# hacklace.net
KiCad netlist of a schematic drawn in EAGLE
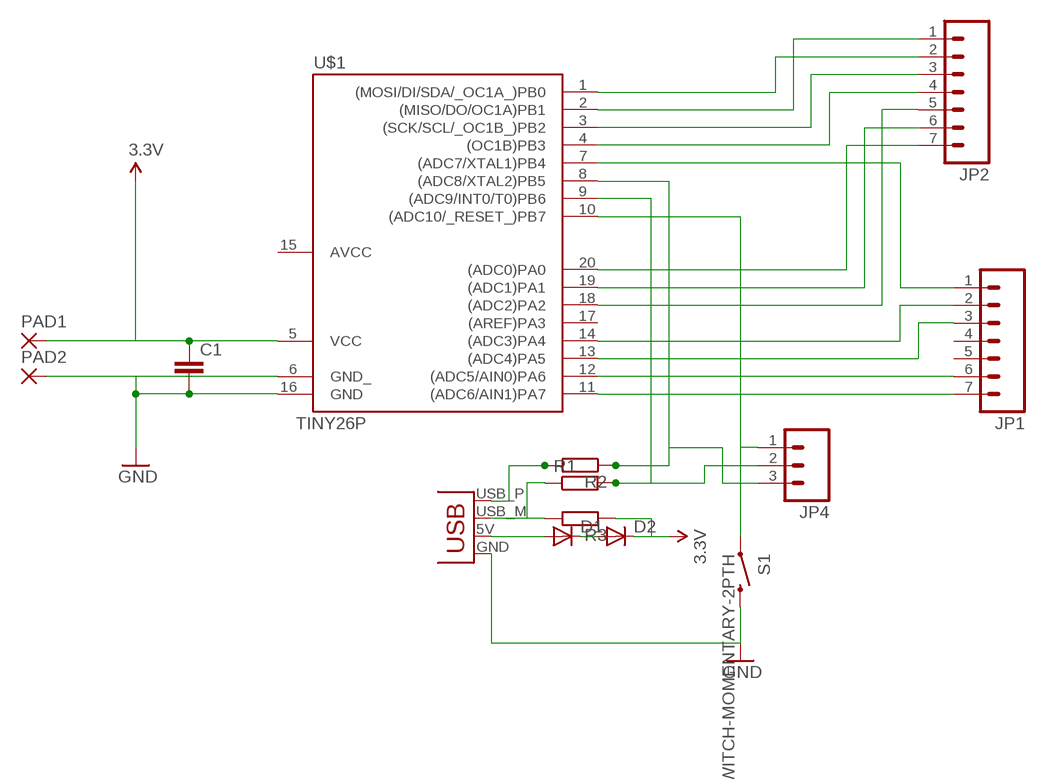
[diagram p0: schematic, sheet 1]

(export (version "E")
  (design (tool "Eeschema 10.0.6"))
  (components
    (comp (ref "C1")
      (value "C-EU025-025X050")
      (footprint "eagle-import:C025-025X050")
      (libsource (lib "eagle-import") (part "C-EU025-025X050"))
    )
    (comp (ref "D1")
      (value "DIODE-D-5")
      (footprint "eagle-import:D-5")
      (libsource (lib "eagle-import") (part "DIODE-D-5"))
    )
    (comp (ref "D2")
      (value "DIODE-D-5")
      (footprint "eagle-import:D-5")
      (libsource (lib "eagle-import") (part "DIODE-D-5"))
    )
    (comp (ref "JP1")
      (value "M07")
      (footprint "eagle-import:1X07")
      (libsource (lib "eagle-import") (part "M07"))
    )
    (comp (ref "JP2")
      (value "M07")
      (footprint "eagle-import:1X07")
      (libsource (lib "eagle-import") (part "M07"))
    )
    (comp (ref "JP3")
      (value "USBPCB")
      (footprint "eagle-import:USB-A-PCB")
      (libsource (lib "eagle-import") (part "USBPCB"))
    )
    (comp (ref "JP4")
      (value "M03PTH")
      (footprint "eagle-import:1X03")
      (libsource (lib "eagle-import") (part "M03PTH"))
    )
    (comp (ref "PAD1")
      (value "1,6/0,8")
      (footprint "eagle-import:1,6_0,8")
      (libsource (lib "eagle-import") (part "1,6/0,8"))
    )
    (comp (ref "PAD2")
      (value "1,6/0,8")
      (footprint "eagle-import:1,6_0,8")
      (libsource (lib "eagle-import") (part "1,6/0,8"))
    )
    (comp (ref "R1")
      (value "R-EU_0204/7")
      (footprint "eagle-import:0204_7")
      (libsource (lib "eagle-import") (part "R-EU_0204/7"))
    )
    (comp (ref "R2")
      (value "R-EU_0204/7")
      (footprint "eagle-import:0204_7")
      (libsource (lib "eagle-import") (part "R-EU_0204/7"))
    )
    (comp (ref "R3")
      (value "R-EU_0204/7")
      (footprint "eagle-import:0204_7")
      (libsource (lib "eagle-import") (part "R-EU_0204/7"))
    )
    (comp (ref "S1")
      (value "SWITCH-MOMENTARY-2PTH")
      (footprint "eagle-import:TACTILE-PTH")
      (libsource (lib "eagle-import") (part "SWITCH-MOMENTARY-2PTH"))
    )
    (comp (ref "U$1")
      (value "TINY26P")
      (footprint "eagle-import:DIL20")
      (libsource (lib "eagle-import") (part "TINY26P"))
    )
  )
  (nets
    (net (code "1") (name "/AVCC") (class "Default")
      (node (ref "U$1") (pin "15") (pinfunction "AVCC_15") (pintype "power_in"))
    )
    (net (code "2") (name "3.3V") (class "Default")
      (node (ref "C1") (pin "1") (pinfunction "1_1") (pintype "passive"))
      (node (ref "D2") (pin "C") (pinfunction "C_C") (pintype "passive"))
      (node (ref "PAD1") (pin "1") (pinfunction "P_1") (pintype "passive"))
      (node (ref "R3") (pin "1") (pinfunction "1_1") (pintype "passive"))
      (node (ref "U$1") (pin "5") (pinfunction "VCC_5") (pintype "power_in"))
    )
    (net (code "3") (name "GND") (class "Default")
      (node (ref "C1") (pin "2") (pinfunction "2_2") (pintype "passive"))
      (node (ref "JP3") (pin "GND") (pinfunction "GND_GND") (pintype "bidirectional"))
      (node (ref "PAD2") (pin "1") (pinfunction "P_1") (pintype "passive"))
      (node (ref "S1") (pin "3") (pinfunction "2_3") (pintype "passive"))
      (node (ref "U$1") (pin "16") (pinfunction "GND_16") (pintype "power_in"))
      (node (ref "U$1") (pin "6") (pinfunction "GND__6") (pintype "power_in"))
    )
    (net (code "4") (name "Net-(D1-PadC)") (class "Default")
      (node (ref "D1") (pin "C") (pinfunction "C_C") (pintype "passive"))
      (node (ref "D2") (pin "A") (pinfunction "A_A") (pintype "passive"))
    )
    (net (code "5") (name "Net-(JP3-D+)") (class "Default")
      (node (ref "JP3") (pin "USB_P") (pinfunction "D+_USB_P") (pintype "bidirectional"))
      (node (ref "R2") (pin "2") (pinfunction "2_2") (pintype "passive"))
    )
    (net (code "6") (name "Net-(JP3-D-)") (class "Default")
      (node (ref "JP3") (pin "USB_M") (pinfunction "D-_USB_M") (pintype "bidirectional"))
      (node (ref "R1") (pin "1") (pinfunction "1_1") (pintype "passive"))
      (node (ref "R3") (pin "2") (pinfunction "2_2") (pintype "passive"))
    )
    (net (code "7") (name "Net-(JP3-VBUS)") (class "Default")
      (node (ref "D1") (pin "A") (pinfunction "A_A") (pintype "passive"))
      (node (ref "JP3") (pin "5V") (pinfunction "VBUS_5V") (pintype "bidirectional"))
    )
    (net (code "8") (name "Net-(U$1-(ADC0)PA0)") (class "Default")
      (node (ref "JP2") (pin "7") (pinfunction "7_7") (pintype "passive"))
      (node (ref "U$1") (pin "20") (pinfunction "(ADC0)PA0_20") (pintype "bidirectional"))
    )
    (net (code "9") (name "Net-(U$1-(ADC1)PA1)") (class "Default")
      (node (ref "JP2") (pin "6") (pinfunction "6_6") (pintype "passive"))
      (node (ref "U$1") (pin "19") (pinfunction "(ADC1)PA1_19") (pintype "bidirectional"))
    )
    (net (code "10") (name "Net-(U$1-(ADC2)PA2)") (class "Default")
      (node (ref "JP2") (pin "5") (pinfunction "5_5") (pintype "passive"))
      (node (ref "U$1") (pin "18") (pinfunction "(ADC2)PA2_18") (pintype "bidirectional"))
    )
    (net (code "11") (name "Net-(U$1-(ADC3)PA4)") (class "Default")
      (node (ref "JP1") (pin "2") (pinfunction "2_2") (pintype "passive"))
      (node (ref "U$1") (pin "14") (pinfunction "(ADC3)PA4_14") (pintype "bidirectional"))
    )
    (net (code "12") (name "Net-(U$1-(ADC4)PA5)") (class "Default")
      (node (ref "JP1") (pin "3") (pinfunction "3_3") (pintype "passive"))
      (node (ref "U$1") (pin "13") (pinfunction "(ADC4)PA5_13") (pintype "bidirectional"))
    )
    (net (code "13") (name "Net-(U$1-(ADC5{slash}AIN0)PA6)") (class "Default")
      (node (ref "JP1") (pin "6") (pinfunction "6_6") (pintype "passive"))
      (node (ref "U$1") (pin "12") (pinfunction "(ADC5/AIN0)PA6_12") (pintype "bidirectional"))
    )
    (net (code "14") (name "Net-(U$1-(ADC6{slash}AIN1)PA7)") (class "Default")
      (node (ref "JP1") (pin "7") (pinfunction "7_7") (pintype "passive"))
      (node (ref "U$1") (pin "11") (pinfunction "(ADC6/AIN1)PA7_11") (pintype "bidirectional"))
    )
    (net (code "15") (name "Net-(U$1-(ADC7{slash}XTAL1)PB4)") (class "Default")
      (node (ref "JP1") (pin "1") (pinfunction "1_1") (pintype "passive"))
      (node (ref "U$1") (pin "7") (pinfunction "(ADC7/XTAL1)PB4_7") (pintype "bidirectional"))
    )
    (net (code "16") (name "Net-(U$1-(ADC8{slash}XTAL2)PB5)") (class "Default")
      (node (ref "JP4") (pin "3") (pinfunction "3_3") (pintype "passive"))
      (node (ref "R2") (pin "1") (pinfunction "1_1") (pintype "passive"))
      (node (ref "U$1") (pin "8") (pinfunction "(ADC8/XTAL2)PB5_8") (pintype "bidirectional"))
    )
    (net (code "17") (name "Net-(U$1-(ADC9{slash}INT0{slash}T0)PB6)") (class "Default")
      (node (ref "JP4") (pin "2") (pinfunction "2_2") (pintype "passive"))
      (node (ref "R1") (pin "2") (pinfunction "2_2") (pintype "passive"))
      (node (ref "U$1") (pin "9") (pinfunction "(ADC9/INT0/T0)PB6_9") (pintype "bidirectional"))
    )
    (net (code "18") (name "Net-(U$1-(ADC10{slash}_RESET_)PB7)") (class "Default")
      (node (ref "JP4") (pin "1") (pinfunction "1_1") (pintype "passive"))
      (node (ref "S1") (pin "1") (pinfunction "1_1") (pintype "passive"))
      (node (ref "U$1") (pin "10") (pinfunction "(ADC10/_RESET_)PB7_10") (pintype "bidirectional"))
    )
    (net (code "19") (name "Net-(U$1-(MISO{slash}DO{slash}OC1A)PB1)") (class "Default")
      (node (ref "JP2") (pin "1") (pinfunction "1_1") (pintype "passive"))
      (node (ref "U$1") (pin "2") (pinfunction "(MISO/DO/OC1A)PB1_2") (pintype "bidirectional"))
    )
    (net (code "20") (name "Net-(U$1-(MOSI{slash}DI{slash}SDA{slash}_OC1A_)PB0)") (class "Default")
      (node (ref "JP2") (pin "2") (pinfunction "2_2") (pintype "passive"))
      (node (ref "U$1") (pin "1") (pinfunction "(MOSI/DI/SDA/_OC1A_)PB0_1") (pintype "bidirectional"))
    )
    (net (code "21") (name "Net-(U$1-(OC1B)PB3)") (class "Default")
      (node (ref "JP2") (pin "4") (pinfunction "4_4") (pintype "passive"))
      (node (ref "U$1") (pin "4") (pinfunction "(OC1B)PB3_4") (pintype "bidirectional"))
    )
    (net (code "22") (name "Net-(U$1-(SCK{slash}SCL{slash}_OC1B_)PB2)") (class "Default")
      (node (ref "JP2") (pin "3") (pinfunction "3_3") (pintype "passive"))
      (node (ref "U$1") (pin "3") (pinfunction "(SCK/SCL/_OC1B_)PB2_3") (pintype "bidirectional"))
    )
    (net (code "23") (name "unconnected-(JP1-Pad4)") (class "Default")
      (node (ref "JP1") (pin "4") (pinfunction "4_4") (pintype "passive"))
    )
    (net (code "24") (name "unconnected-(JP1-Pad5)") (class "Default")
      (node (ref "JP1") (pin "5") (pinfunction "5_5") (pintype "passive"))
    )
    (net (code "25") (name "unconnected-(U$1-(AREF)PA3-Pad17)") (class "Default")
      (node (ref "U$1") (pin "17") (pinfunction "(AREF)PA3_17") (pintype "bidirectional"))
    )
  )
)
